# SCH_pls_work_not_lose_2022-07-18.net
KiCad netlist of a schematic drawn in EasyEDA
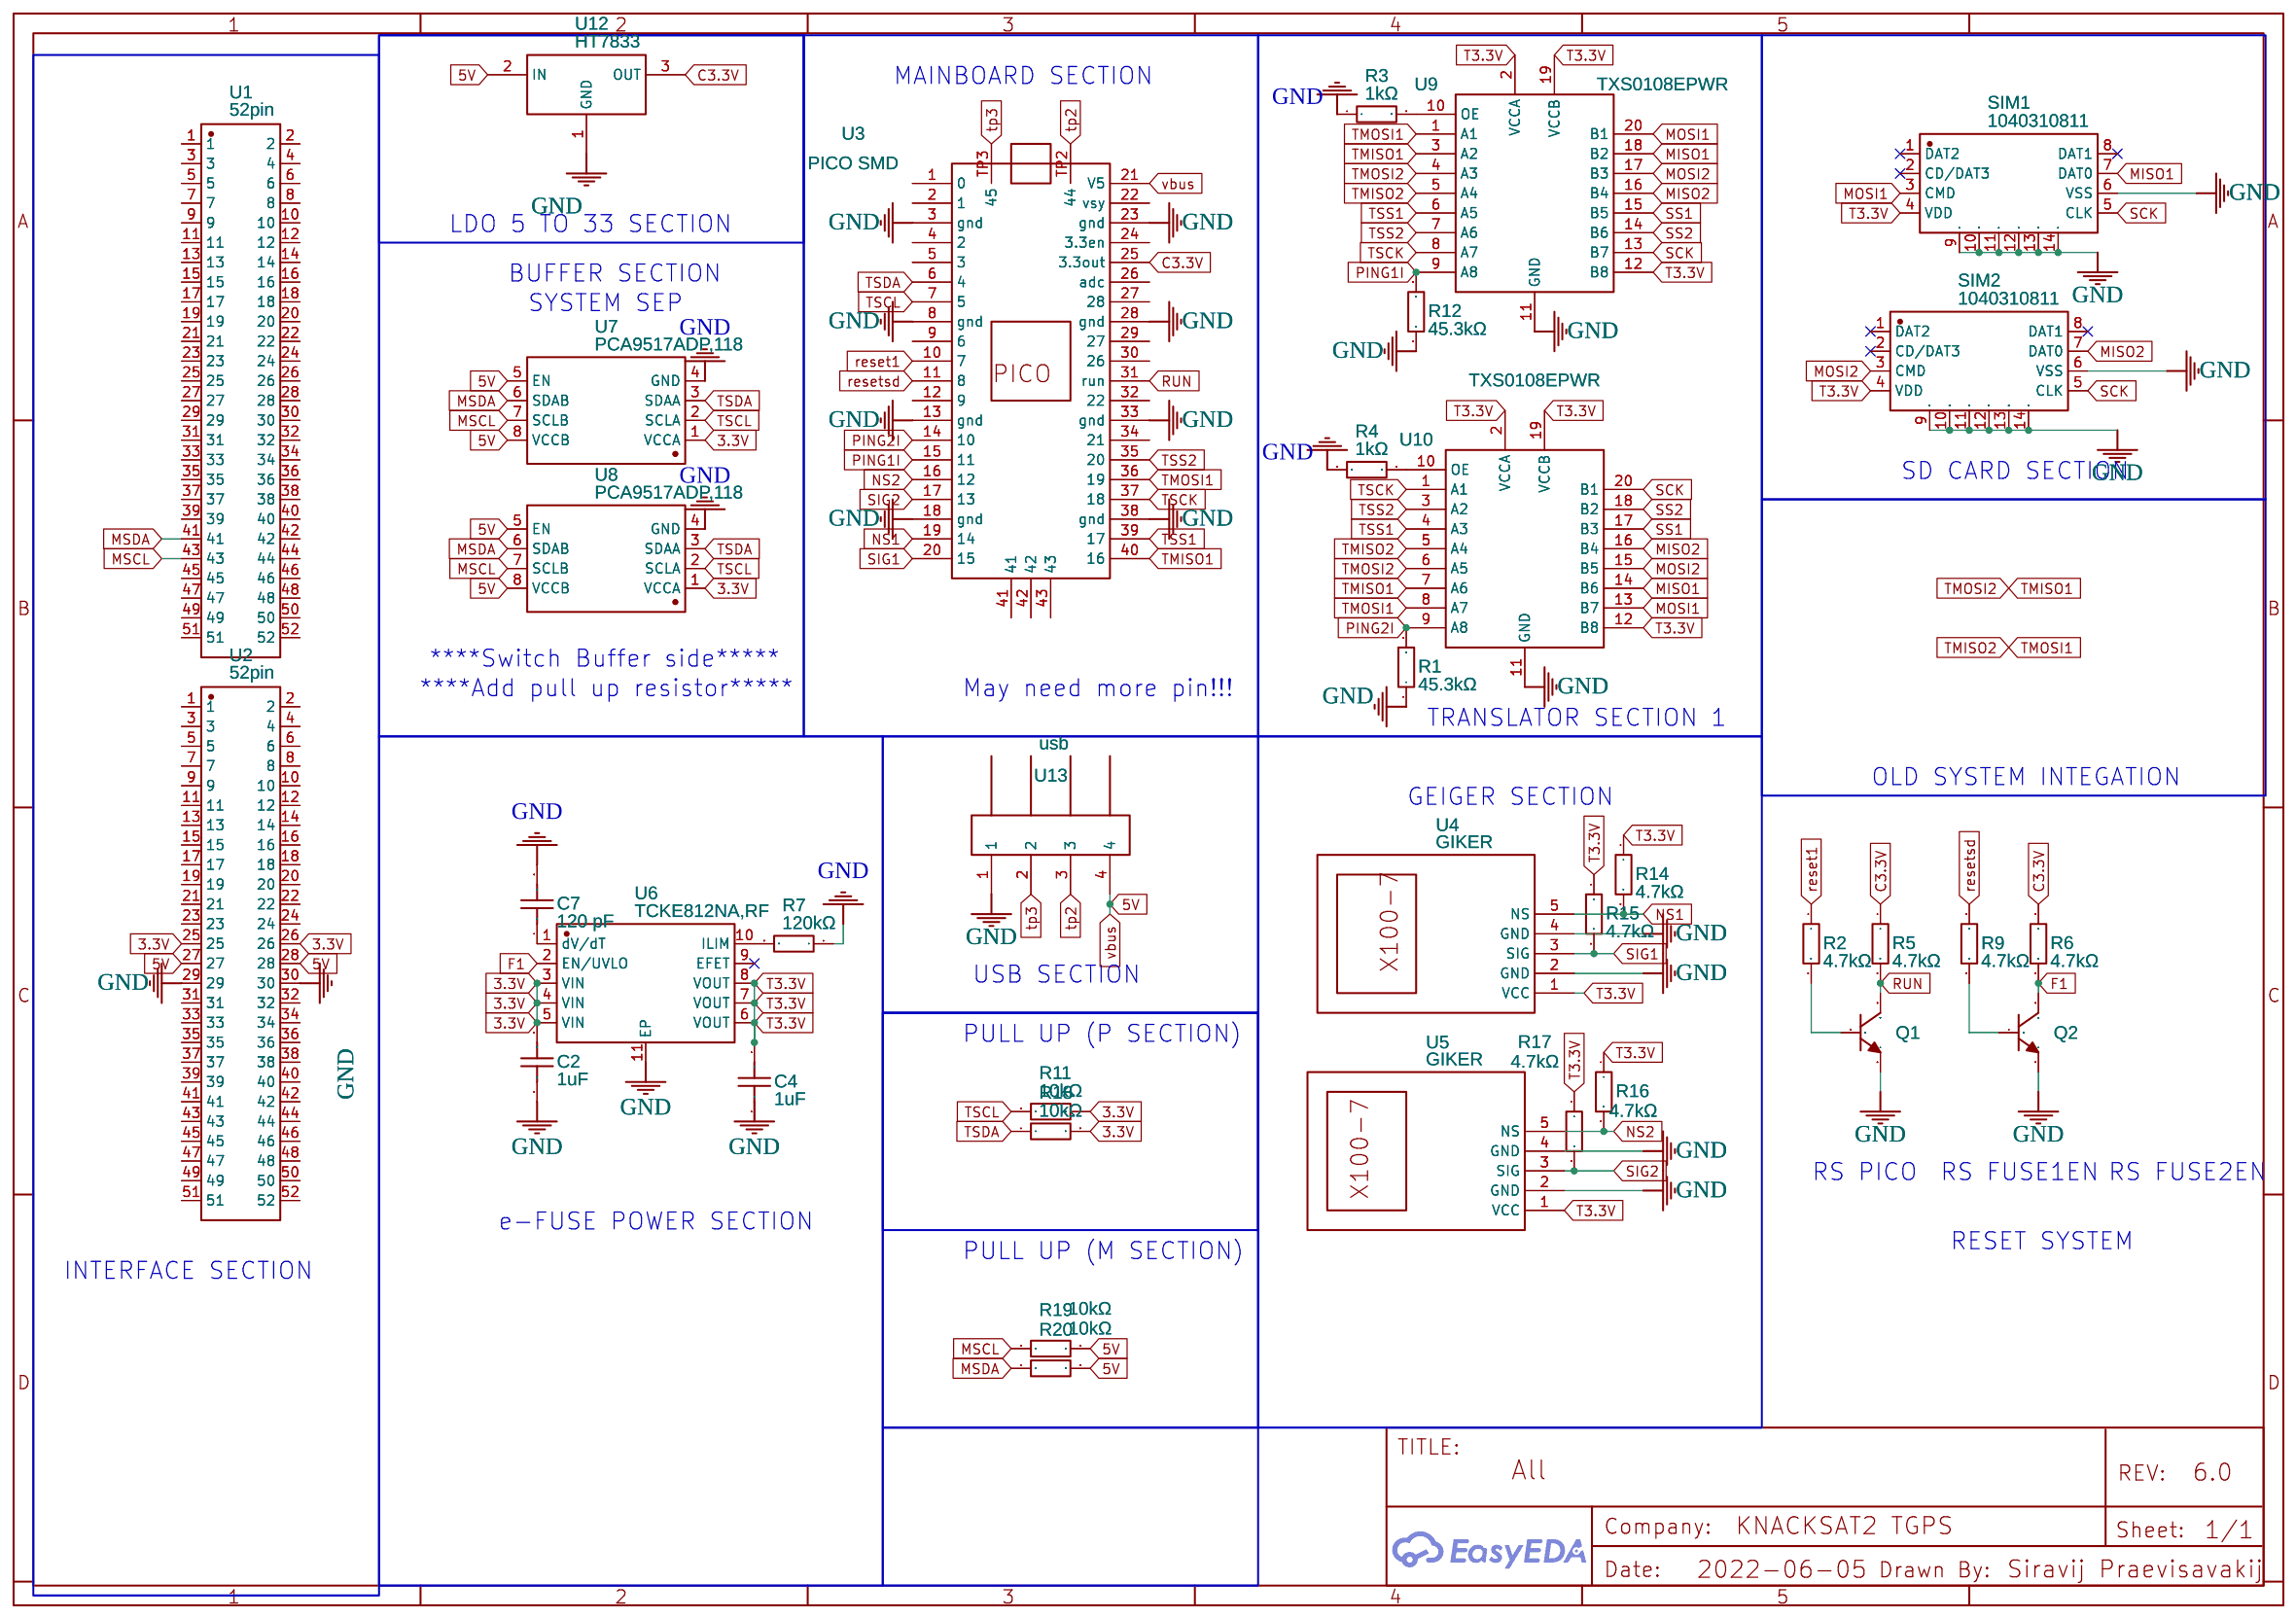
[diagram p0: schematic sheet]

(export (version "E")
  (design (tool "Eeschema 10.0.6"))
  (components
    (comp (ref "C2") (value "1uF") (libsource (lib "") (part "C_0603_US")))
    (comp (ref "C4") (value "1uF") (libsource (lib "") (part "C_0603_US")))
    (comp (ref "C7") (value "120 pF") (libsource (lib "") (part "C_0603_US")))
    (comp (ref "Q1")
      (value "2SC3324-BL(TE85L,F")
      (fields (field (name "BOM_Supplier Part") "C2999171"))
      (libsource (lib "") (part "2SC3324-BL(TE85L,F"))
    )
    (comp (ref "Q2")
      (value "2SC3324-BL(TE85L,F")
      (fields (field (name "BOM_Supplier Part") "C2999171"))
      (libsource (lib "") (part "2SC3324-BL(TE85L,F"))
    )
    (comp (ref "R1")
      (value "45.3kΩ")
      (fields
        (field (name "BOM_Manufacturer Part") "RMC040245.3K1%N")
        (field (name "BOM_Supplier Part") "C325554")
      )
      (libsource (lib "") (part "RMC040245.3K1%N"))
    )
    (comp (ref "R2")
      (value "4.7kΩ")
      (fields
        (field (name "BOM_Manufacturer Part") "RMC08054.7K1%N")
        (field (name "BOM_Supplier Part") "C269746")
      )
      (libsource (lib "") (part "RMC08054.7K1%N"))
    )
    (comp (ref "R3")
      (value "1kΩ")
      (fields
        (field (name "BOM_Manufacturer Part") "PTFR0805B1K00N9")
        (field (name "BOM_Supplier Part") "C328437")
      )
      (libsource (lib "") (part "PTFR0805B1K00N9"))
    )
    (comp (ref "R4")
      (value "1kΩ")
      (fields
        (field (name "BOM_Manufacturer Part") "PTFR0805B1K00N9")
        (field (name "BOM_Supplier Part") "C328437")
      )
      (libsource (lib "") (part "PTFR0805B1K00N9"))
    )
    (comp (ref "R5")
      (value "4.7kΩ")
      (fields
        (field (name "BOM_Manufacturer Part") "RMC08054.7K1%N")
        (field (name "BOM_Supplier Part") "C269746")
      )
      (libsource (lib "") (part "RMC08054.7K1%N"))
    )
    (comp (ref "R6")
      (value "4.7kΩ")
      (fields
        (field (name "BOM_Manufacturer Part") "RMC08054.7K1%N")
        (field (name "BOM_Supplier Part") "C269746")
      )
      (libsource (lib "") (part "RMC08054.7K1%N"))
    )
    (comp (ref "R7")
      (value "120kΩ")
      (fields
        (field (name "BOM_Manufacturer Part") "RMC0402120K1%N")
        (field (name "BOM_Supplier Part") "C325558")
      )
      (libsource (lib "") (part "RMC0402120K1%N"))
    )
    (comp (ref "R9")
      (value "4.7kΩ")
      (fields
        (field (name "BOM_Manufacturer Part") "RMC08054.7K1%N")
        (field (name "BOM_Supplier Part") "C269746")
      )
      (libsource (lib "") (part "RMC08054.7K1%N"))
    )
    (comp (ref "R11")
      (value "10kΩ")
      (fields
        (field (name "BOM_Manufacturer Part") "AECR0805F10K0K9")
        (field (name "BOM_Supplier Part") "C328381")
      )
      (libsource (lib "") (part "AECR0805F10K0K9"))
    )
    (comp (ref "R12")
      (value "45.3kΩ")
      (fields
        (field (name "BOM_Manufacturer Part") "RMC040245.3K1%N")
        (field (name "BOM_Supplier Part") "C325554")
      )
      (libsource (lib "") (part "RMC040245.3K1%N"))
    )
    (comp (ref "R14")
      (value "4.7kΩ")
      (fields
        (field (name "BOM_Manufacturer Part") "RMC08054.7K1%N")
        (field (name "BOM_Supplier Part") "C269746")
      )
      (libsource (lib "") (part "RMC08054.7K1%N"))
    )
    (comp (ref "R15")
      (value "4.7kΩ")
      (fields
        (field (name "BOM_Manufacturer Part") "RMC08054.7K1%N")
        (field (name "BOM_Supplier Part") "C269746")
      )
      (libsource (lib "") (part "RMC08054.7K1%N"))
    )
    (comp (ref "R16")
      (value "4.7kΩ")
      (fields
        (field (name "BOM_Manufacturer Part") "RMC08054.7K1%N")
        (field (name "BOM_Supplier Part") "C269746")
      )
      (libsource (lib "") (part "RMC08054.7K1%N"))
    )
    (comp (ref "R17")
      (value "4.7kΩ")
      (fields
        (field (name "BOM_Manufacturer Part") "RMC08054.7K1%N")
        (field (name "BOM_Supplier Part") "C269746")
      )
      (libsource (lib "") (part "RMC08054.7K1%N"))
    )
    (comp (ref "R18")
      (value "10kΩ")
      (fields
        (field (name "BOM_Manufacturer Part") "AECR0805F10K0K9")
        (field (name "BOM_Supplier Part") "C328381")
      )
      (libsource (lib "") (part "AECR0805F10K0K9"))
    )
    (comp (ref "R19")
      (value "10kΩ")
      (fields
        (field (name "BOM_Manufacturer Part") "AECR0805F10K0K9")
        (field (name "BOM_Supplier Part") "C328381")
      )
      (libsource (lib "") (part "AECR0805F10K0K9"))
    )
    (comp (ref "R20")
      (value "10kΩ")
      (fields
        (field (name "BOM_Manufacturer Part") "AECR0805F10K0K9")
        (field (name "BOM_Supplier Part") "C328381")
      )
      (libsource (lib "") (part "AECR0805F10K0K9"))
    )
    (comp (ref "SIM1")
      (value "1040310811")
      (fields (field (name "BOM_Supplier Part") "C585350"))
      (libsource (lib "") (part "1040310811"))
    )
    (comp (ref "SIM2")
      (value "1040310811")
      (fields (field (name "BOM_Supplier Part") "C585350"))
      (libsource (lib "") (part "1040310811"))
    )
    (comp (ref "U1") (value "52pin") (libsource (lib "") (part "52pin")))
    (comp (ref "U2") (value "52pin") (libsource (lib "") (part "52pin")))
    (comp (ref "U3") (value "PICO SMD") (libsource (lib "") (part "PICO SMD")))
    (comp (ref "U4") (value "GIKER") (libsource (lib "") (part "GIKER_1")))
    (comp (ref "U5") (value "GIKER") (libsource (lib "") (part "GIKER")))
    (comp (ref "U6")
      (value "TCKE812NA,RF")
      (fields (field (name "BOM_Supplier Part") "C1880271"))
      (libsource (lib "") (part "TCKE812NA,RF"))
    )
    (comp (ref "U7")
      (value "PCA9517ADP,118")
      (fields (field (name "BOM_Supplier Part") "C80799"))
      (libsource (lib "") (part "PCA9517ADP,118"))
    )
    (comp (ref "U8")
      (value "PCA9517ADP,118")
      (fields (field (name "BOM_Supplier Part") "C80799"))
      (libsource (lib "") (part "PCA9517ADP,118"))
    )
    (comp (ref "U9")
      (value "TXS0108EPWR")
      (fields (field (name "BOM_Supplier Part") "C17206"))
      (libsource (lib "") (part "TXS0108EPWR"))
    )
    (comp (ref "U10")
      (value "TXS0108EPWR")
      (fields (field (name "BOM_Supplier Part") "C17206"))
      (libsource (lib "") (part "TXS0108EPWR"))
    )
    (comp (ref "U12")
      (value "HT7833")
      (fields (field (name "BOM_Supplier Part") "C50936"))
      (libsource (lib "") (part "HT7833"))
    )
    (comp (ref "U13") (value "usb") (libsource (lib "") (part "usb")))
  )
  (nets
    (net (code "1") (name "3.3V") (class "Default")
      (node (ref "C2") (pin "2") (pinfunction "2_2") (pintype "unspecified"))
      (node (ref "R11") (pin "2") (pinfunction "2_2") (pintype "unspecified"))
      (node (ref "R18") (pin "2") (pinfunction "2_2") (pintype "unspecified"))
      (node (ref "U2") (pin "25") (pinfunction "25_25") (pintype "unspecified"))
      (node (ref "U2") (pin "26") (pinfunction "26_26") (pintype "unspecified"))
      (node (ref "U6") (pin "3") (pinfunction "VIN_3") (pintype "unspecified"))
      (node (ref "U6") (pin "4") (pinfunction "VIN_4") (pintype "unspecified"))
      (node (ref "U6") (pin "5") (pinfunction "VIN_5") (pintype "unspecified"))
      (node (ref "U7") (pin "1") (pinfunction "VCCA_1") (pintype "unspecified"))
      (node (ref "U8") (pin "1") (pinfunction "VCCA_1") (pintype "unspecified"))
    )
    (net (code "2") (name "5V") (class "Default")
      (node (ref "R19") (pin "2") (pinfunction "2_2") (pintype "unspecified"))
      (node (ref "R20") (pin "2") (pinfunction "2_2") (pintype "unspecified"))
      (node (ref "U12") (pin "2") (pinfunction "IN_2") (pintype "passive"))
      (node (ref "U13") (pin "4") (pinfunction "4_4") (pintype "unspecified"))
      (node (ref "U2") (pin "27") (pinfunction "27_27") (pintype "unspecified"))
      (node (ref "U2") (pin "28") (pinfunction "28_28") (pintype "unspecified"))
      (node (ref "U3") (pin "21") (pinfunction "V5_21") (pintype "unspecified"))
      (node (ref "U7") (pin "5") (pinfunction "EN_5") (pintype "unspecified"))
      (node (ref "U7") (pin "8") (pinfunction "VCCB_8") (pintype "unspecified"))
      (node (ref "U8") (pin "5") (pinfunction "EN_5") (pintype "unspecified"))
      (node (ref "U8") (pin "8") (pinfunction "VCCB_8") (pintype "unspecified"))
    )
    (net (code "3") (name "C3.3V") (class "Default")
      (node (ref "R5") (pin "1") (pinfunction "1_1") (pintype "unspecified"))
      (node (ref "R6") (pin "1") (pinfunction "1_1") (pintype "unspecified"))
      (node (ref "U12") (pin "3") (pinfunction "OUT_3") (pintype "passive"))
      (node (ref "U3") (pin "25") (pinfunction "3.3out_25") (pintype "unspecified"))
    )
    (net (code "4") (name "F1") (class "Default")
      (node (ref "Q2") (pin "3") (pinfunction "C_3") (pintype "unspecified"))
      (node (ref "R6") (pin "2") (pinfunction "2_2") (pintype "unspecified"))
      (node (ref "U6") (pin "2") (pinfunction "EN/UVLO_2") (pintype "unspecified"))
    )
    (net (code "5") (name "GND") (class "Default")
      (node (ref "C2") (pin "1") (pinfunction "1_1") (pintype "unspecified"))
      (node (ref "C4") (pin "1") (pinfunction "1_1") (pintype "unspecified"))
      (node (ref "C7") (pin "2") (pinfunction "2_2") (pintype "unspecified"))
      (node (ref "Q1") (pin "2") (pinfunction "E_2") (pintype "unspecified"))
      (node (ref "Q2") (pin "2") (pinfunction "E_2") (pintype "unspecified"))
      (node (ref "R1") (pin "1") (pinfunction "1_1") (pintype "unspecified"))
      (node (ref "R12") (pin "1") (pinfunction "1_1") (pintype "unspecified"))
      (node (ref "R3") (pin "1") (pinfunction "1_1") (pintype "unspecified"))
      (node (ref "R4") (pin "1") (pinfunction "1_1") (pintype "unspecified"))
      (node (ref "R7") (pin "1") (pinfunction "1_1") (pintype "unspecified"))
      (node (ref "SIM1") (pin "10") (pinfunction "10_10") (pintype "unspecified"))
      (node (ref "SIM1") (pin "11") (pinfunction "11_11") (pintype "unspecified"))
      (node (ref "SIM1") (pin "12") (pinfunction "12_12") (pintype "unspecified"))
      (node (ref "SIM1") (pin "13") (pinfunction "13_13") (pintype "unspecified"))
      (node (ref "SIM1") (pin "14") (pinfunction "14_14") (pintype "unspecified"))
      (node (ref "SIM1") (pin "6") (pinfunction "VSS_6") (pintype "unspecified"))
      (node (ref "SIM1") (pin "9") (pinfunction "9_9") (pintype "unspecified"))
      (node (ref "SIM2") (pin "10") (pinfunction "10_10") (pintype "unspecified"))
      (node (ref "SIM2") (pin "11") (pinfunction "11_11") (pintype "unspecified"))
      (node (ref "SIM2") (pin "12") (pinfunction "12_12") (pintype "unspecified"))
      (node (ref "SIM2") (pin "13") (pinfunction "13_13") (pintype "unspecified"))
      (node (ref "SIM2") (pin "14") (pinfunction "14_14") (pintype "unspecified"))
      (node (ref "SIM2") (pin "6") (pinfunction "VSS_6") (pintype "unspecified"))
      (node (ref "SIM2") (pin "9") (pinfunction "9_9") (pintype "unspecified"))
      (node (ref "U10") (pin "11") (pinfunction "GND_11") (pintype "unspecified"))
      (node (ref "U12") (pin "1") (pinfunction "GND_1") (pintype "passive"))
      (node (ref "U13") (pin "1") (pinfunction "1_1") (pintype "unspecified"))
      (node (ref "U2") (pin "29") (pinfunction "29_29") (pintype "unspecified"))
      (node (ref "U2") (pin "30") (pinfunction "30_30") (pintype "unspecified"))
      (node (ref "U3") (pin "13") (pinfunction "gnd_13") (pintype "unspecified"))
      (node (ref "U3") (pin "18") (pinfunction "gnd_18") (pintype "unspecified"))
      (node (ref "U3") (pin "23") (pinfunction "gnd_23") (pintype "unspecified"))
      (node (ref "U3") (pin "28") (pinfunction "gnd_28") (pintype "unspecified"))
      (node (ref "U3") (pin "3") (pinfunction "gnd_3") (pintype "unspecified"))
      (node (ref "U3") (pin "33") (pinfunction "gnd_33") (pintype "unspecified"))
      (node (ref "U3") (pin "38") (pinfunction "gnd_38") (pintype "unspecified"))
      (node (ref "U3") (pin "8") (pinfunction "gnd_8") (pintype "unspecified"))
      (node (ref "U4") (pin "2") (pinfunction "GND_2") (pintype "unspecified"))
      (node (ref "U4") (pin "4") (pinfunction "GND_4") (pintype "unspecified"))
      (node (ref "U5") (pin "2") (pinfunction "GND_2") (pintype "unspecified"))
      (node (ref "U5") (pin "4") (pinfunction "GND_4") (pintype "unspecified"))
      (node (ref "U6") (pin "11") (pinfunction "EP_11") (pintype "unspecified"))
      (node (ref "U7") (pin "4") (pinfunction "GND_4") (pintype "unspecified"))
      (node (ref "U8") (pin "4") (pinfunction "GND_4") (pintype "unspecified"))
      (node (ref "U9") (pin "11") (pinfunction "GND_11") (pintype "unspecified"))
    )
    (net (code "6") (name "MISO1") (class "Default")
      (node (ref "SIM1") (pin "7") (pinfunction "DAT0_7") (pintype "unspecified"))
      (node (ref "U10") (pin "14") (pinfunction "B6_14") (pintype "unspecified"))
      (node (ref "U9") (pin "18") (pinfunction "B2_18") (pintype "unspecified"))
    )
    (net (code "7") (name "MISO2") (class "Default")
      (node (ref "SIM2") (pin "7") (pinfunction "DAT0_7") (pintype "unspecified"))
      (node (ref "U10") (pin "16") (pinfunction "B4_16") (pintype "unspecified"))
      (node (ref "U9") (pin "16") (pinfunction "B4_16") (pintype "unspecified"))
    )
    (net (code "8") (name "MOSI1") (class "Default")
      (node (ref "SIM1") (pin "3") (pinfunction "CMD_3") (pintype "unspecified"))
      (node (ref "U10") (pin "13") (pinfunction "B7_13") (pintype "unspecified"))
      (node (ref "U9") (pin "20") (pinfunction "B1_20") (pintype "unspecified"))
    )
    (net (code "9") (name "MOSI2") (class "Default")
      (node (ref "SIM2") (pin "3") (pinfunction "CMD_3") (pintype "unspecified"))
      (node (ref "U10") (pin "15") (pinfunction "B5_15") (pintype "unspecified"))
      (node (ref "U9") (pin "17") (pinfunction "B3_17") (pintype "unspecified"))
    )
    (net (code "10") (name "MSCL") (class "Default")
      (node (ref "R19") (pin "1") (pinfunction "1_1") (pintype "unspecified"))
      (node (ref "U1") (pin "43") (pinfunction "43_43") (pintype "unspecified"))
      (node (ref "U7") (pin "7") (pinfunction "SCLB_7") (pintype "unspecified"))
      (node (ref "U8") (pin "7") (pinfunction "SCLB_7") (pintype "unspecified"))
    )
    (net (code "11") (name "MSDA") (class "Default")
      (node (ref "R20") (pin "1") (pinfunction "1_1") (pintype "unspecified"))
      (node (ref "U1") (pin "41") (pinfunction "41_41") (pintype "unspecified"))
      (node (ref "U7") (pin "6") (pinfunction "SDAB_6") (pintype "unspecified"))
      (node (ref "U8") (pin "6") (pinfunction "SDAB_6") (pintype "unspecified"))
    )
    (net (code "12") (name "NS1") (class "Default")
      (node (ref "R14") (pin "2") (pinfunction "2_2") (pintype "unspecified"))
      (node (ref "U3") (pin "19") (pinfunction "14_19") (pintype "unspecified"))
      (node (ref "U4") (pin "5") (pinfunction "NS_5") (pintype "unspecified"))
    )
    (net (code "13") (name "NS2") (class "Default")
      (node (ref "R16") (pin "2") (pinfunction "2_2") (pintype "unspecified"))
      (node (ref "U3") (pin "16") (pinfunction "12_16") (pintype "unspecified"))
      (node (ref "U5") (pin "5") (pinfunction "NS_5") (pintype "unspecified"))
    )
    (net (code "14") (name "Net-(Q1-B)") (class "Default")
      (node (ref "Q1") (pin "1") (pinfunction "B_1") (pintype "unspecified"))
      (node (ref "R2") (pin "2") (pinfunction "2_2") (pintype "unspecified"))
    )
    (net (code "15") (name "Net-(Q2-B)") (class "Default")
      (node (ref "Q2") (pin "1") (pinfunction "B_1") (pintype "unspecified"))
      (node (ref "R9") (pin "2") (pinfunction "2_2") (pintype "unspecified"))
    )
    (net (code "16") (name "Net-(U6-ILIM)") (class "Default")
      (node (ref "R7") (pin "2") (pinfunction "2_2") (pintype "unspecified"))
      (node (ref "U6") (pin "10") (pinfunction "ILIM_10") (pintype "unspecified"))
    )
    (net (code "17") (name "Net-(U6-dV{slash}dT)") (class "Default")
      (node (ref "C7") (pin "1") (pinfunction "1_1") (pintype "unspecified"))
      (node (ref "U6") (pin "1") (pinfunction "dV/dT_1") (pintype "unspecified"))
    )
    (net (code "18") (name "Net-(U9-OE)") (class "Default")
      (node (ref "R3") (pin "2") (pinfunction "2_2") (pintype "unspecified"))
      (node (ref "U9") (pin "10") (pinfunction "OE_10") (pintype "unspecified"))
    )
    (net (code "19") (name "Net-(U10-OE)") (class "Default")
      (node (ref "R4") (pin "2") (pinfunction "2_2") (pintype "unspecified"))
      (node (ref "U10") (pin "10") (pinfunction "OE_10") (pintype "unspecified"))
    )
    (net (code "20") (name "PING1I") (class "Default")
      (node (ref "R12") (pin "2") (pinfunction "2_2") (pintype "unspecified"))
      (node (ref "U3") (pin "15") (pinfunction "11_15") (pintype "unspecified"))
      (node (ref "U9") (pin "9") (pinfunction "A8_9") (pintype "unspecified"))
    )
    (net (code "21") (name "PING2I") (class "Default")
      (node (ref "R1") (pin "2") (pinfunction "2_2") (pintype "unspecified"))
      (node (ref "U10") (pin "9") (pinfunction "A8_9") (pintype "unspecified"))
      (node (ref "U3") (pin "14") (pinfunction "10_14") (pintype "unspecified"))
    )
    (net (code "22") (name "RUN") (class "Default")
      (node (ref "Q1") (pin "3") (pinfunction "C_3") (pintype "unspecified"))
      (node (ref "R5") (pin "2") (pinfunction "2_2") (pintype "unspecified"))
      (node (ref "U3") (pin "31") (pinfunction "run_31") (pintype "unspecified"))
    )
    (net (code "23") (name "SCK") (class "Default")
      (node (ref "SIM1") (pin "5") (pinfunction "CLK_5") (pintype "unspecified"))
      (node (ref "SIM2") (pin "5") (pinfunction "CLK_5") (pintype "unspecified"))
      (node (ref "U10") (pin "20") (pinfunction "B1_20") (pintype "unspecified"))
      (node (ref "U9") (pin "13") (pinfunction "B7_13") (pintype "unspecified"))
    )
    (net (code "24") (name "SIG1") (class "Default")
      (node (ref "R15") (pin "2") (pinfunction "2_2") (pintype "unspecified"))
      (node (ref "U3") (pin "20") (pinfunction "15_20") (pintype "unspecified"))
      (node (ref "U4") (pin "3") (pinfunction "SIG_3") (pintype "unspecified"))
    )
    (net (code "25") (name "SIG2") (class "Default")
      (node (ref "R17") (pin "2") (pinfunction "2_2") (pintype "unspecified"))
      (node (ref "U3") (pin "17") (pinfunction "13_17") (pintype "unspecified"))
      (node (ref "U5") (pin "3") (pinfunction "SIG_3") (pintype "unspecified"))
    )
    (net (code "26") (name "SS1") (class "Default")
      (node (ref "U10") (pin "17") (pinfunction "B3_17") (pintype "unspecified"))
      (node (ref "U9") (pin "15") (pinfunction "B5_15") (pintype "unspecified"))
    )
    (net (code "27") (name "SS2") (class "Default")
      (node (ref "U10") (pin "18") (pinfunction "B2_18") (pintype "unspecified"))
      (node (ref "U9") (pin "14") (pinfunction "B6_14") (pintype "unspecified"))
    )
    (net (code "28") (name "T3.3V") (class "Default")
      (node (ref "C4") (pin "2") (pinfunction "2_2") (pintype "unspecified"))
      (node (ref "R14") (pin "1") (pinfunction "1_1") (pintype "unspecified"))
      (node (ref "R15") (pin "1") (pinfunction "1_1") (pintype "unspecified"))
      (node (ref "R16") (pin "1") (pinfunction "1_1") (pintype "unspecified"))
      (node (ref "R17") (pin "1") (pinfunction "1_1") (pintype "unspecified"))
      (node (ref "SIM1") (pin "4") (pinfunction "VDD_4") (pintype "unspecified"))
      (node (ref "SIM2") (pin "4") (pinfunction "VDD_4") (pintype "unspecified"))
      (node (ref "U10") (pin "12") (pinfunction "B8_12") (pintype "unspecified"))
      (node (ref "U10") (pin "19") (pinfunction "VCCB_19") (pintype "unspecified"))
      (node (ref "U10") (pin "2") (pinfunction "VCCA_2") (pintype "unspecified"))
      (node (ref "U4") (pin "1") (pinfunction "VCC_1") (pintype "unspecified"))
      (node (ref "U5") (pin "1") (pinfunction "VCC_1") (pintype "unspecified"))
      (node (ref "U6") (pin "6") (pinfunction "VOUT_6") (pintype "unspecified"))
      (node (ref "U6") (pin "7") (pinfunction "VOUT_7") (pintype "unspecified"))
      (node (ref "U6") (pin "8") (pinfunction "VOUT_8") (pintype "unspecified"))
      (node (ref "U9") (pin "12") (pinfunction "B8_12") (pintype "unspecified"))
      (node (ref "U9") (pin "19") (pinfunction "VCCB_19") (pintype "unspecified"))
      (node (ref "U9") (pin "2") (pinfunction "VCCA_2") (pintype "unspecified"))
    )
    (net (code "29") (name "TMISO1") (class "Default")
      (node (ref "U10") (pin "6") (pinfunction "A5_6") (pintype "unspecified"))
      (node (ref "U10") (pin "7") (pinfunction "A6_7") (pintype "unspecified"))
      (node (ref "U3") (pin "40") (pinfunction "16_40") (pintype "unspecified"))
      (node (ref "U9") (pin "3") (pinfunction "A2_3") (pintype "unspecified"))
      (node (ref "U9") (pin "4") (pinfunction "A3_4") (pintype "unspecified"))
    )
    (net (code "30") (name "TMISO2") (class "Default")
      (node (ref "U10") (pin "5") (pinfunction "A4_5") (pintype "unspecified"))
      (node (ref "U10") (pin "8") (pinfunction "A7_8") (pintype "unspecified"))
      (node (ref "U3") (pin "36") (pinfunction "19_36") (pintype "unspecified"))
      (node (ref "U9") (pin "1") (pinfunction "A1_1") (pintype "unspecified"))
      (node (ref "U9") (pin "5") (pinfunction "A4_5") (pintype "unspecified"))
    )
    (net (code "31") (name "TSCK") (class "Default")
      (node (ref "U10") (pin "1") (pinfunction "A1_1") (pintype "unspecified"))
      (node (ref "U3") (pin "37") (pinfunction "18_37") (pintype "unspecified"))
      (node (ref "U9") (pin "8") (pinfunction "A7_8") (pintype "unspecified"))
    )
    (net (code "32") (name "TSCL") (class "Default")
      (node (ref "R11") (pin "1") (pinfunction "1_1") (pintype "unspecified"))
      (node (ref "U3") (pin "7") (pinfunction "5_7") (pintype "unspecified"))
      (node (ref "U7") (pin "2") (pinfunction "SCLA_2") (pintype "unspecified"))
      (node (ref "U8") (pin "2") (pinfunction "SCLA_2") (pintype "unspecified"))
    )
    (net (code "33") (name "TSDA") (class "Default")
      (node (ref "R18") (pin "1") (pinfunction "1_1") (pintype "unspecified"))
      (node (ref "U3") (pin "6") (pinfunction "4_6") (pintype "unspecified"))
      (node (ref "U7") (pin "3") (pinfunction "SDAA_3") (pintype "unspecified"))
      (node (ref "U8") (pin "3") (pinfunction "SDAA_3") (pintype "unspecified"))
    )
    (net (code "34") (name "TSS1") (class "Default")
      (node (ref "U10") (pin "4") (pinfunction "A3_4") (pintype "unspecified"))
      (node (ref "U3") (pin "39") (pinfunction "17_39") (pintype "unspecified"))
      (node (ref "U9") (pin "6") (pinfunction "A5_6") (pintype "unspecified"))
    )
    (net (code "35") (name "TSS2") (class "Default")
      (node (ref "U10") (pin "3") (pinfunction "A2_3") (pintype "unspecified"))
      (node (ref "U3") (pin "35") (pinfunction "20_35") (pintype "unspecified"))
      (node (ref "U9") (pin "7") (pinfunction "A6_7") (pintype "unspecified"))
    )
    (net (code "36") (name "reset1") (class "Default")
      (node (ref "R2") (pin "1") (pinfunction "1_1") (pintype "unspecified"))
      (node (ref "U3") (pin "10") (pinfunction "7_10") (pintype "unspecified"))
    )
    (net (code "37") (name "resetsd") (class "Default")
      (node (ref "R9") (pin "1") (pinfunction "1_1") (pintype "unspecified"))
      (node (ref "U3") (pin "11") (pinfunction "8_11") (pintype "unspecified"))
    )
    (net (code "38") (name "tp2") (class "Default")
      (node (ref "U13") (pin "3") (pinfunction "3_3") (pintype "unspecified"))
      (node (ref "U3") (pin "TP2") (pinfunction "44_TP2") (pintype "unspecified"))
    )
    (net (code "39") (name "tp3") (class "Default")
      (node (ref "U13") (pin "2") (pinfunction "2_2") (pintype "unspecified"))
      (node (ref "U3") (pin "TP3") (pinfunction "45_TP3") (pintype "unspecified"))
    )
    (net (code "40") (name "unconnected-(SIM1-CD{slash}DAT3-Pad2)") (class "Default")
      (node (ref "SIM1") (pin "2") (pinfunction "CD/DAT3_2") (pintype "unspecified+no_connect"))
    )
    (net (code "41") (name "unconnected-(SIM1-DAT1-Pad8)") (class "Default")
      (node (ref "SIM1") (pin "8") (pinfunction "DAT1_8") (pintype "unspecified+no_connect"))
    )
    (net (code "42") (name "unconnected-(SIM1-DAT2-Pad1)") (class "Default")
      (node (ref "SIM1") (pin "1") (pinfunction "DAT2_1") (pintype "unspecified+no_connect"))
    )
    (net (code "43") (name "unconnected-(SIM2-CD{slash}DAT3-Pad2)") (class "Default")
      (node (ref "SIM2") (pin "2") (pinfunction "CD/DAT3_2") (pintype "unspecified+no_connect"))
    )
    (net (code "44") (name "unconnected-(SIM2-DAT1-Pad8)") (class "Default")
      (node (ref "SIM2") (pin "8") (pinfunction "DAT1_8") (pintype "unspecified+no_connect"))
    )
    (net (code "45") (name "unconnected-(SIM2-DAT2-Pad1)") (class "Default")
      (node (ref "SIM2") (pin "1") (pinfunction "DAT2_1") (pintype "unspecified+no_connect"))
    )
    (net (code "46") (name "unconnected-(U1-Pad1)") (class "Default")
      (node (ref "U1") (pin "1") (pinfunction "1_1") (pintype "unspecified"))
    )
    (net (code "47") (name "unconnected-(U1-Pad2)") (class "Default")
      (node (ref "U1") (pin "2") (pinfunction "2_2") (pintype "unspecified"))
    )
    (net (code "48") (name "unconnected-(U1-Pad3)") (class "Default")
      (node (ref "U1") (pin "3") (pinfunction "3_3") (pintype "unspecified"))
    )
    (net (code "49") (name "unconnected-(U1-Pad4)") (class "Default")
      (node (ref "U1") (pin "4") (pinfunction "4_4") (pintype "unspecified"))
    )
    (net (code "50") (name "unconnected-(U1-Pad5)") (class "Default")
      (node (ref "U1") (pin "5") (pinfunction "5_5") (pintype "unspecified"))
    )
    (net (code "51") (name "unconnected-(U1-Pad6)") (class "Default")
      (node (ref "U1") (pin "6") (pinfunction "6_6") (pintype "unspecified"))
    )
    (net (code "52") (name "unconnected-(U1-Pad7)") (class "Default")
      (node (ref "U1") (pin "7") (pinfunction "7_7") (pintype "unspecified"))
    )
    (net (code "53") (name "unconnected-(U1-Pad8)") (class "Default")
      (node (ref "U1") (pin "8") (pinfunction "8_8") (pintype "unspecified"))
    )
    (net (code "54") (name "unconnected-(U1-Pad9)") (class "Default")
      (node (ref "U1") (pin "9") (pinfunction "9_9") (pintype "unspecified"))
    )
    (net (code "55") (name "unconnected-(U1-Pad10)") (class "Default")
      (node (ref "U1") (pin "10") (pinfunction "10_10") (pintype "unspecified"))
    )
    (net (code "56") (name "unconnected-(U1-Pad11)") (class "Default")
      (node (ref "U1") (pin "11") (pinfunction "11_11") (pintype "unspecified"))
    )
    (net (code "57") (name "unconnected-(U1-Pad12)") (class "Default")
      (node (ref "U1") (pin "12") (pinfunction "12_12") (pintype "unspecified"))
    )
    (net (code "58") (name "unconnected-(U1-Pad13)") (class "Default")
      (node (ref "U1") (pin "13") (pinfunction "13_13") (pintype "unspecified"))
    )
    (net (code "59") (name "unconnected-(U1-Pad14)") (class "Default")
      (node (ref "U1") (pin "14") (pinfunction "14_14") (pintype "unspecified"))
    )
    (net (code "60") (name "unconnected-(U1-Pad15)") (class "Default")
      (node (ref "U1") (pin "15") (pinfunction "15_15") (pintype "unspecified"))
    )
    (net (code "61") (name "unconnected-(U1-Pad16)") (class "Default")
      (node (ref "U1") (pin "16") (pinfunction "16_16") (pintype "unspecified"))
    )
    (net (code "62") (name "unconnected-(U1-Pad17)") (class "Default")
      (node (ref "U1") (pin "17") (pinfunction "17_17") (pintype "unspecified"))
    )
    (net (code "63") (name "unconnected-(U1-Pad18)") (class "Default")
      (node (ref "U1") (pin "18") (pinfunction "18_18") (pintype "unspecified"))
    )
    (net (code "64") (name "unconnected-(U1-Pad19)") (class "Default")
      (node (ref "U1") (pin "19") (pinfunction "19_19") (pintype "unspecified"))
    )
    (net (code "65") (name "unconnected-(U1-Pad20)") (class "Default")
      (node (ref "U1") (pin "20") (pinfunction "20_20") (pintype "unspecified"))
    )
    (net (code "66") (name "unconnected-(U1-Pad21)") (class "Default")
      (node (ref "U1") (pin "21") (pinfunction "21_21") (pintype "unspecified"))
    )
    (net (code "67") (name "unconnected-(U1-Pad22)") (class "Default")
      (node (ref "U1") (pin "22") (pinfunction "22_22") (pintype "unspecified"))
    )
    (net (code "68") (name "unconnected-(U1-Pad23)") (class "Default")
      (node (ref "U1") (pin "23") (pinfunction "23_23") (pintype "unspecified"))
    )
    (net (code "69") (name "unconnected-(U1-Pad24)") (class "Default")
      (node (ref "U1") (pin "24") (pinfunction "24_24") (pintype "unspecified"))
    )
    (net (code "70") (name "unconnected-(U1-Pad25)") (class "Default")
      (node (ref "U1") (pin "25") (pinfunction "25_25") (pintype "unspecified"))
    )
    (net (code "71") (name "unconnected-(U1-Pad26)") (class "Default")
      (node (ref "U1") (pin "26") (pinfunction "26_26") (pintype "unspecified"))
    )
    (net (code "72") (name "unconnected-(U1-Pad27)") (class "Default")
      (node (ref "U1") (pin "27") (pinfunction "27_27") (pintype "unspecified"))
    )
    (net (code "73") (name "unconnected-(U1-Pad28)") (class "Default")
      (node (ref "U1") (pin "28") (pinfunction "28_28") (pintype "unspecified"))
    )
    (net (code "74") (name "unconnected-(U1-Pad29)") (class "Default")
      (node (ref "U1") (pin "29") (pinfunction "29_29") (pintype "unspecified"))
    )
    (net (code "75") (name "unconnected-(U1-Pad30)") (class "Default")
      (node (ref "U1") (pin "30") (pinfunction "30_30") (pintype "unspecified"))
    )
    (net (code "76") (name "unconnected-(U1-Pad31)") (class "Default")
      (node (ref "U1") (pin "31") (pinfunction "31_31") (pintype "unspecified"))
    )
    (net (code "77") (name "unconnected-(U1-Pad32)") (class "Default")
      (node (ref "U1") (pin "32") (pinfunction "32_32") (pintype "unspecified"))
    )
    (net (code "78") (name "unconnected-(U1-Pad33)") (class "Default")
      (node (ref "U1") (pin "33") (pinfunction "33_33") (pintype "unspecified"))
    )
    (net (code "79") (name "unconnected-(U1-Pad34)") (class "Default")
      (node (ref "U1") (pin "34") (pinfunction "34_34") (pintype "unspecified"))
    )
    (net (code "80") (name "unconnected-(U1-Pad35)") (class "Default")
      (node (ref "U1") (pin "35") (pinfunction "35_35") (pintype "unspecified"))
    )
    (net (code "81") (name "unconnected-(U1-Pad36)") (class "Default")
      (node (ref "U1") (pin "36") (pinfunction "36_36") (pintype "unspecified"))
    )
    (net (code "82") (name "unconnected-(U1-Pad37)") (class "Default")
      (node (ref "U1") (pin "37") (pinfunction "37_37") (pintype "unspecified"))
    )
    (net (code "83") (name "unconnected-(U1-Pad38)") (class "Default")
      (node (ref "U1") (pin "38") (pinfunction "38_38") (pintype "unspecified"))
    )
    (net (code "84") (name "unconnected-(U1-Pad39)") (class "Default")
      (node (ref "U1") (pin "39") (pinfunction "39_39") (pintype "unspecified"))
    )
    (net (code "85") (name "unconnected-(U1-Pad40)") (class "Default")
      (node (ref "U1") (pin "40") (pinfunction "40_40") (pintype "unspecified"))
    )
    (net (code "86") (name "unconnected-(U1-Pad42)") (class "Default")
      (node (ref "U1") (pin "42") (pinfunction "42_42") (pintype "unspecified"))
    )
    (net (code "87") (name "unconnected-(U1-Pad44)") (class "Default")
      (node (ref "U1") (pin "44") (pinfunction "44_44") (pintype "unspecified"))
    )
    (net (code "88") (name "unconnected-(U1-Pad45)") (class "Default")
      (node (ref "U1") (pin "45") (pinfunction "45_45") (pintype "unspecified"))
    )
    (net (code "89") (name "unconnected-(U1-Pad46)") (class "Default")
      (node (ref "U1") (pin "46") (pinfunction "46_46") (pintype "unspecified"))
    )
    (net (code "90") (name "unconnected-(U1-Pad47)") (class "Default")
      (node (ref "U1") (pin "47") (pinfunction "47_47") (pintype "unspecified"))
    )
    (net (code "91") (name "unconnected-(U1-Pad48)") (class "Default")
      (node (ref "U1") (pin "48") (pinfunction "48_48") (pintype "unspecified"))
    )
    (net (code "92") (name "unconnected-(U1-Pad49)") (class "Default")
      (node (ref "U1") (pin "49") (pinfunction "49_49") (pintype "unspecified"))
    )
    (net (code "93") (name "unconnected-(U1-Pad50)") (class "Default")
      (node (ref "U1") (pin "50") (pinfunction "50_50") (pintype "unspecified"))
    )
    (net (code "94") (name "unconnected-(U1-Pad51)") (class "Default")
      (node (ref "U1") (pin "51") (pinfunction "51_51") (pintype "unspecified"))
    )
    (net (code "95") (name "unconnected-(U1-Pad52)") (class "Default")
      (node (ref "U1") (pin "52") (pinfunction "52_52") (pintype "unspecified"))
    )
    (net (code "96") (name "unconnected-(U2-Pad1)") (class "Default")
      (node (ref "U2") (pin "1") (pinfunction "1_1") (pintype "unspecified"))
    )
    (net (code "97") (name "unconnected-(U2-Pad2)") (class "Default")
      (node (ref "U2") (pin "2") (pinfunction "2_2") (pintype "unspecified"))
    )
    (net (code "98") (name "unconnected-(U2-Pad3)") (class "Default")
      (node (ref "U2") (pin "3") (pinfunction "3_3") (pintype "unspecified"))
    )
    (net (code "99") (name "unconnected-(U2-Pad4)") (class "Default")
      (node (ref "U2") (pin "4") (pinfunction "4_4") (pintype "unspecified"))
    )
    (net (code "100") (name "unconnected-(U2-Pad5)") (class "Default")
      (node (ref "U2") (pin "5") (pinfunction "5_5") (pintype "unspecified"))
    )
    (net (code "101") (name "unconnected-(U2-Pad6)") (class "Default")
      (node (ref "U2") (pin "6") (pinfunction "6_6") (pintype "unspecified"))
    )
    (net (code "102") (name "unconnected-(U2-Pad7)") (class "Default")
      (node (ref "U2") (pin "7") (pinfunction "7_7") (pintype "unspecified"))
    )
    (net (code "103") (name "unconnected-(U2-Pad8)") (class "Default")
      (node (ref "U2") (pin "8") (pinfunction "8_8") (pintype "unspecified"))
    )
    (net (code "104") (name "unconnected-(U2-Pad9)") (class "Default")
      (node (ref "U2") (pin "9") (pinfunction "9_9") (pintype "unspecified"))
    )
    (net (code "105") (name "unconnected-(U2-Pad10)") (class "Default")
      (node (ref "U2") (pin "10") (pinfunction "10_10") (pintype "unspecified"))
    )
    (net (code "106") (name "unconnected-(U2-Pad11)") (class "Default")
      (node (ref "U2") (pin "11") (pinfunction "11_11") (pintype "unspecified"))
    )
    (net (code "107") (name "unconnected-(U2-Pad12)") (class "Default")
      (node (ref "U2") (pin "12") (pinfunction "12_12") (pintype "unspecified"))
    )
    (net (code "108") (name "unconnected-(U2-Pad13)") (class "Default")
      (node (ref "U2") (pin "13") (pinfunction "13_13") (pintype "unspecified"))
    )
    (net (code "109") (name "unconnected-(U2-Pad14)") (class "Default")
      (node (ref "U2") (pin "14") (pinfunction "14_14") (pintype "unspecified"))
    )
    (net (code "110") (name "unconnected-(U2-Pad15)") (class "Default")
      (node (ref "U2") (pin "15") (pinfunction "15_15") (pintype "unspecified"))
    )
    (net (code "111") (name "unconnected-(U2-Pad16)") (class "Default")
      (node (ref "U2") (pin "16") (pinfunction "16_16") (pintype "unspecified"))
    )
    (net (code "112") (name "unconnected-(U2-Pad17)") (class "Default")
      (node (ref "U2") (pin "17") (pinfunction "17_17") (pintype "unspecified"))
    )
    (net (code "113") (name "unconnected-(U2-Pad18)") (class "Default")
      (node (ref "U2") (pin "18") (pinfunction "18_18") (pintype "unspecified"))
    )
    (net (code "114") (name "unconnected-(U2-Pad19)") (class "Default")
      (node (ref "U2") (pin "19") (pinfunction "19_19") (pintype "unspecified"))
    )
    (net (code "115") (name "unconnected-(U2-Pad20)") (class "Default")
      (node (ref "U2") (pin "20") (pinfunction "20_20") (pintype "unspecified"))
    )
    (net (code "116") (name "unconnected-(U2-Pad21)") (class "Default")
      (node (ref "U2") (pin "21") (pinfunction "21_21") (pintype "unspecified"))
    )
    (net (code "117") (name "unconnected-(U2-Pad22)") (class "Default")
      (node (ref "U2") (pin "22") (pinfunction "22_22") (pintype "unspecified"))
    )
    (net (code "118") (name "unconnected-(U2-Pad23)") (class "Default")
      (node (ref "U2") (pin "23") (pinfunction "23_23") (pintype "unspecified"))
    )
    (net (code "119") (name "unconnected-(U2-Pad24)") (class "Default")
      (node (ref "U2") (pin "24") (pinfunction "24_24") (pintype "unspecified"))
    )
    (net (code "120") (name "unconnected-(U2-Pad31)") (class "Default")
      (node (ref "U2") (pin "31") (pinfunction "31_31") (pintype "unspecified"))
    )
    (net (code "121") (name "unconnected-(U2-Pad32)") (class "Default")
      (node (ref "U2") (pin "32") (pinfunction "32_32") (pintype "unspecified"))
    )
    (net (code "122") (name "unconnected-(U2-Pad33)") (class "Default")
      (node (ref "U2") (pin "33") (pinfunction "33_33") (pintype "unspecified"))
    )
    (net (code "123") (name "unconnected-(U2-Pad34)") (class "Default")
      (node (ref "U2") (pin "34") (pinfunction "34_34") (pintype "unspecified"))
    )
    (net (code "124") (name "unconnected-(U2-Pad35)") (class "Default")
      (node (ref "U2") (pin "35") (pinfunction "35_35") (pintype "unspecified"))
    )
    (net (code "125") (name "unconnected-(U2-Pad36)") (class "Default")
      (node (ref "U2") (pin "36") (pinfunction "36_36") (pintype "unspecified"))
    )
    (net (code "126") (name "unconnected-(U2-Pad37)") (class "Default")
      (node (ref "U2") (pin "37") (pinfunction "37_37") (pintype "unspecified"))
    )
    (net (code "127") (name "unconnected-(U2-Pad38)") (class "Default")
      (node (ref "U2") (pin "38") (pinfunction "38_38") (pintype "unspecified"))
    )
    (net (code "128") (name "unconnected-(U2-Pad39)") (class "Default")
      (node (ref "U2") (pin "39") (pinfunction "39_39") (pintype "unspecified"))
    )
    (net (code "129") (name "unconnected-(U2-Pad40)") (class "Default")
      (node (ref "U2") (pin "40") (pinfunction "40_40") (pintype "unspecified"))
    )
    (net (code "130") (name "unconnected-(U2-Pad41)") (class "Default")
      (node (ref "U2") (pin "41") (pinfunction "41_41") (pintype "unspecified"))
    )
    (net (code "131") (name "unconnected-(U2-Pad42)") (class "Default")
      (node (ref "U2") (pin "42") (pinfunction "42_42") (pintype "unspecified"))
    )
    (net (code "132") (name "unconnected-(U2-Pad43)") (class "Default")
      (node (ref "U2") (pin "43") (pinfunction "43_43") (pintype "unspecified"))
    )
    (net (code "133") (name "unconnected-(U2-Pad44)") (class "Default")
      (node (ref "U2") (pin "44") (pinfunction "44_44") (pintype "unspecified"))
    )
    (net (code "134") (name "unconnected-(U2-Pad45)") (class "Default")
      (node (ref "U2") (pin "45") (pinfunction "45_45") (pintype "unspecified"))
    )
    (net (code "135") (name "unconnected-(U2-Pad46)") (class "Default")
      (node (ref "U2") (pin "46") (pinfunction "46_46") (pintype "unspecified"))
    )
    (net (code "136") (name "unconnected-(U2-Pad47)") (class "Default")
      (node (ref "U2") (pin "47") (pinfunction "47_47") (pintype "unspecified"))
    )
    (net (code "137") (name "unconnected-(U2-Pad48)") (class "Default")
      (node (ref "U2") (pin "48") (pinfunction "48_48") (pintype "unspecified"))
    )
    (net (code "138") (name "unconnected-(U2-Pad49)") (class "Default")
      (node (ref "U2") (pin "49") (pinfunction "49_49") (pintype "unspecified"))
    )
    (net (code "139") (name "unconnected-(U2-Pad50)") (class "Default")
      (node (ref "U2") (pin "50") (pinfunction "50_50") (pintype "unspecified"))
    )
    (net (code "140") (name "unconnected-(U2-Pad51)") (class "Default")
      (node (ref "U2") (pin "51") (pinfunction "51_51") (pintype "unspecified"))
    )
    (net (code "141") (name "unconnected-(U2-Pad52)") (class "Default")
      (node (ref "U2") (pin "52") (pinfunction "52_52") (pintype "unspecified"))
    )
    (net (code "142") (name "unconnected-(U3-0-Pad1)") (class "Default")
      (node (ref "U3") (pin "1") (pinfunction "0_1") (pintype "unspecified"))
    )
    (net (code "143") (name "unconnected-(U3-1-Pad2)") (class "Default")
      (node (ref "U3") (pin "2") (pinfunction "1_2") (pintype "unspecified"))
    )
    (net (code "144") (name "unconnected-(U3-2-Pad4)") (class "Default")
      (node (ref "U3") (pin "4") (pinfunction "2_4") (pintype "unspecified"))
    )
    (net (code "145") (name "unconnected-(U3-3-Pad5)") (class "Default")
      (node (ref "U3") (pin "5") (pinfunction "3_5") (pintype "unspecified"))
    )
    (net (code "146") (name "unconnected-(U3-3.3en-Pad24)") (class "Default")
      (node (ref "U3") (pin "24") (pinfunction "3.3en_24") (pintype "unspecified"))
    )
    (net (code "147") (name "unconnected-(U3-6-Pad9)") (class "Default")
      (node (ref "U3") (pin "9") (pinfunction "6_9") (pintype "unspecified"))
    )
    (net (code "148") (name "unconnected-(U3-9-Pad12)") (class "Default")
      (node (ref "U3") (pin "12") (pinfunction "9_12") (pintype "unspecified"))
    )
    (net (code "149") (name "unconnected-(U3-21-Pad34)") (class "Default")
      (node (ref "U3") (pin "34") (pinfunction "21_34") (pintype "unspecified"))
    )
    (net (code "150") (name "unconnected-(U3-22-Pad32)") (class "Default")
      (node (ref "U3") (pin "32") (pinfunction "22_32") (pintype "unspecified"))
    )
    (net (code "151") (name "unconnected-(U3-26-Pad30)") (class "Default")
      (node (ref "U3") (pin "30") (pinfunction "26_30") (pintype "unspecified"))
    )
    (net (code "152") (name "unconnected-(U3-27-Pad29)") (class "Default")
      (node (ref "U3") (pin "29") (pinfunction "27_29") (pintype "unspecified"))
    )
    (net (code "153") (name "unconnected-(U3-28-Pad27)") (class "Default")
      (node (ref "U3") (pin "27") (pinfunction "28_27") (pintype "unspecified"))
    )
    (net (code "154") (name "unconnected-(U3-Pad41)") (class "Default")
      (node (ref "U3") (pin "41") (pinfunction "41_41") (pintype "unspecified"))
    )
    (net (code "155") (name "unconnected-(U3-Pad42)") (class "Default")
      (node (ref "U3") (pin "42") (pinfunction "42_42") (pintype "unspecified"))
    )
    (net (code "156") (name "unconnected-(U3-Pad43)") (class "Default")
      (node (ref "U3") (pin "43") (pinfunction "43_43") (pintype "unspecified"))
    )
    (net (code "157") (name "unconnected-(U3-adc-Pad26)") (class "Default")
      (node (ref "U3") (pin "26") (pinfunction "adc_26") (pintype "unspecified"))
    )
    (net (code "158") (name "unconnected-(U3-vsy-Pad22)") (class "Default")
      (node (ref "U3") (pin "22") (pinfunction "vsy_22") (pintype "unspecified"))
    )
    (net (code "159") (name "unconnected-(U6-EFET-Pad9)") (class "Default")
      (node (ref "U6") (pin "9") (pinfunction "EFET_9") (pintype "unspecified+no_connect"))
    )
  )
)
